# Prototype_0_2.net
KiCad netlist of a schematic drawn in EAGLE
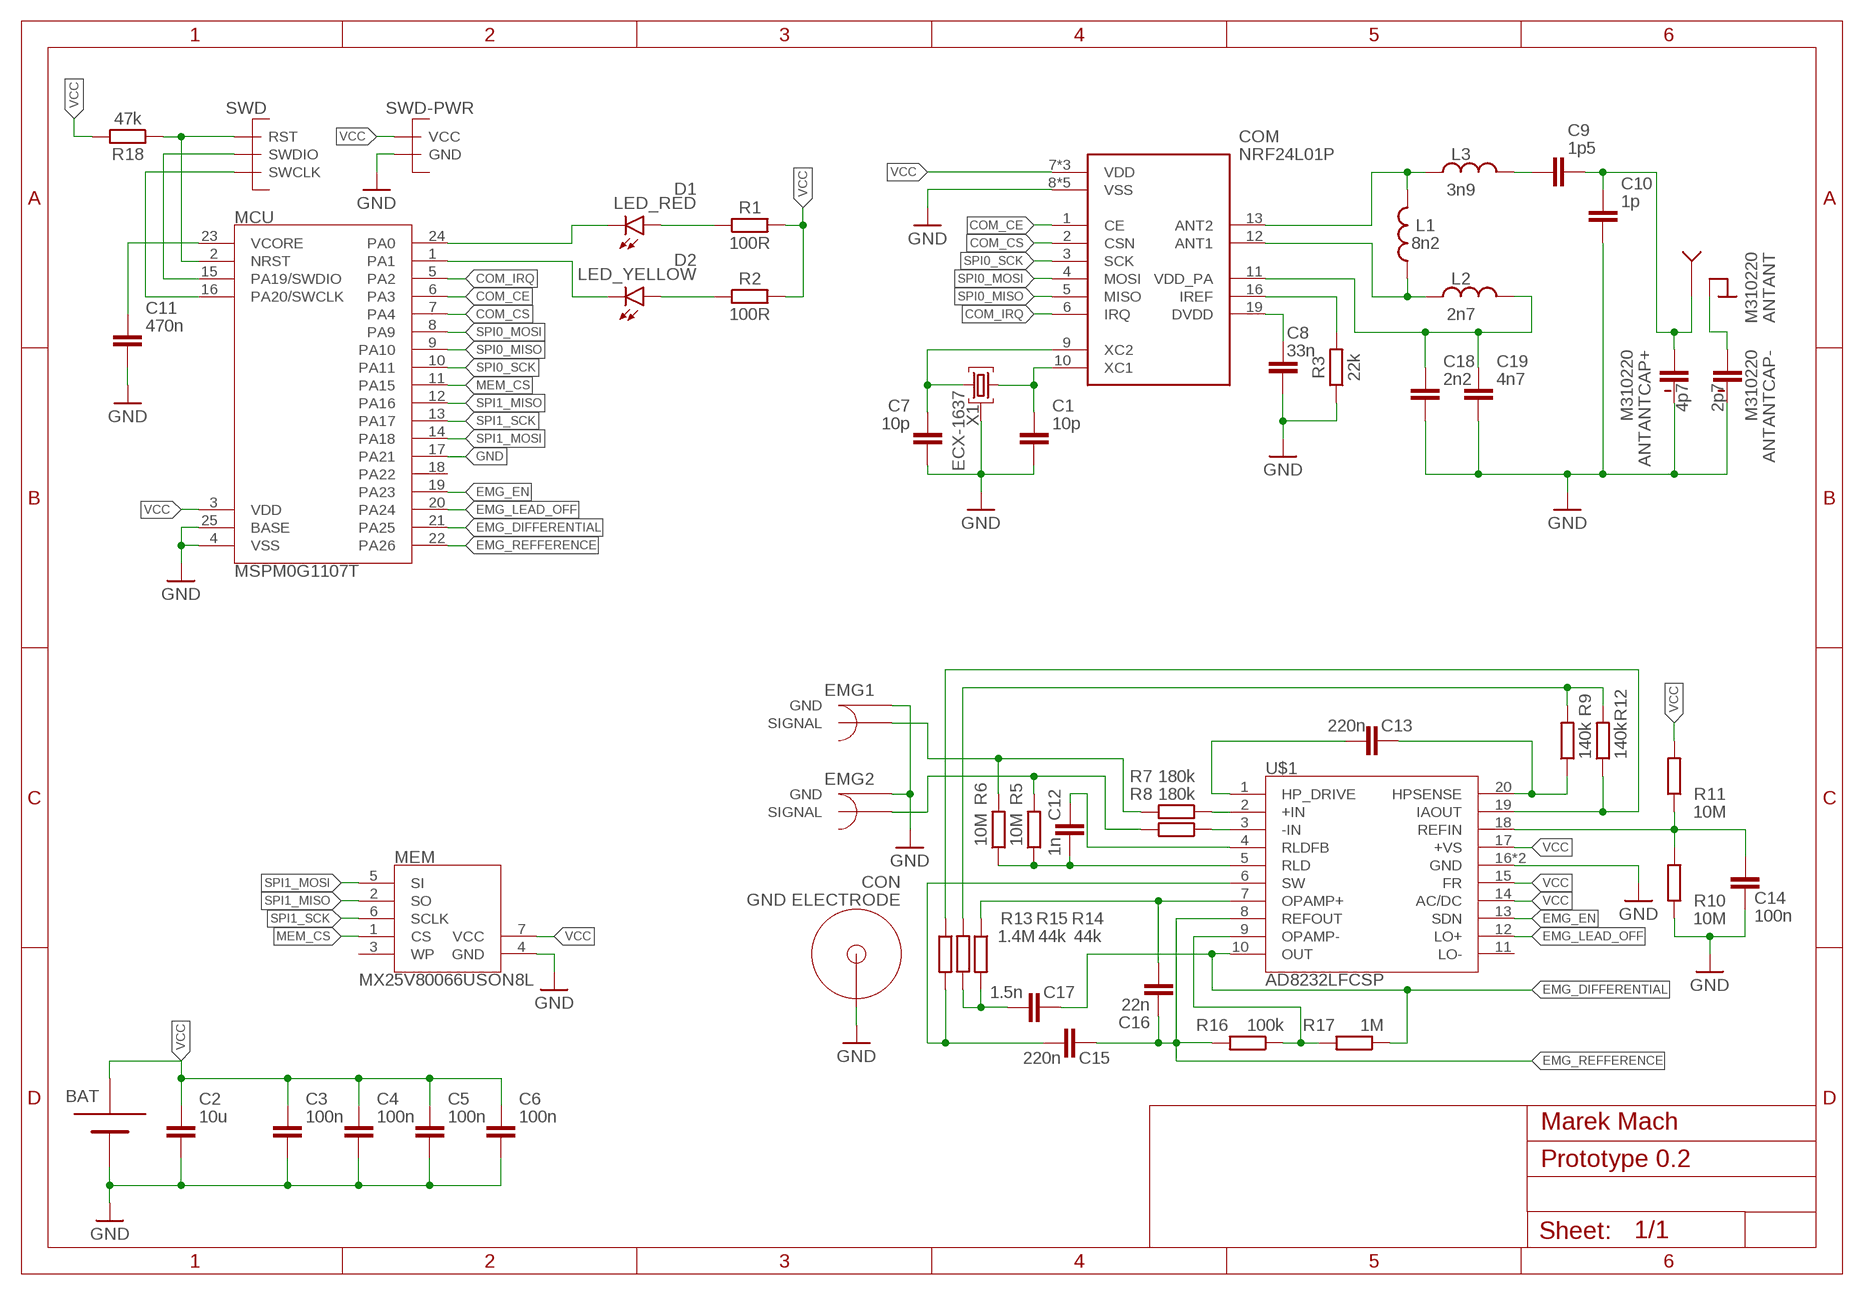
[diagram p0: schematic, sheet 1]

(export (version "E")
  (design (tool "Eeschema 10.0.6"))
  (components
    (comp (ref "ANT")
      (value "M310220")
      (footprint "eagle-import:M310220")
      (libsource (lib "eagle-import") (part "M310220"))
    )
    (comp (ref "BAT")
      (value "2025BAT-HLD-005-THM")
      (footprint "eagle-import:BAT-HLD-005-THM")
      (libsource (lib "eagle-import") (part "2025BAT-HLD-005-THM"))
    )
    (comp (ref "C1")
      (value "10p")
      (footprint "eagle-import:CAPC1005X60")
      (libsource (lib "eagle-import") (part "CCHIP-0402(1005-METRIC)_"))
    )
    (comp (ref "C2")
      (value "10u")
      (footprint "eagle-import:CAPC1608X85")
      (libsource (lib "eagle-import") (part "CCHIP-0603(1608-METRIC)_"))
    )
    (comp (ref "C3")
      (value "100n")
      (footprint "eagle-import:CAPC1608X85")
      (libsource (lib "eagle-import") (part "CCHIP-0603(1608-METRIC)_"))
    )
    (comp (ref "C4")
      (value "100n")
      (footprint "eagle-import:CAPC1608X85")
      (libsource (lib "eagle-import") (part "CCHIP-0603(1608-METRIC)_"))
    )
    (comp (ref "C5")
      (value "100n")
      (footprint "eagle-import:CAPC1608X85")
      (libsource (lib "eagle-import") (part "CCHIP-0603(1608-METRIC)_"))
    )
    (comp (ref "C6")
      (value "100n")
      (footprint "eagle-import:CAPC1608X85")
      (libsource (lib "eagle-import") (part "CCHIP-0603(1608-METRIC)_"))
    )
    (comp (ref "C7")
      (value "10p")
      (footprint "eagle-import:CAPC1005X60")
      (libsource (lib "eagle-import") (part "CCHIP-0402(1005-METRIC)_"))
    )
    (comp (ref "C8")
      (value "33n")
      (footprint "eagle-import:CAPC1005X60")
      (libsource (lib "eagle-import") (part "CCHIP-0402(1005-METRIC)_"))
    )
    (comp (ref "C9")
      (value "1p5")
      (footprint "eagle-import:CAPC1005X60")
      (libsource (lib "eagle-import") (part "CCHIP-0402(1005-METRIC)_"))
    )
    (comp (ref "C10")
      (value "1p")
      (footprint "eagle-import:CAPC1005X60")
      (libsource (lib "eagle-import") (part "CCHIP-0402(1005-METRIC)_"))
    )
    (comp (ref "C11")
      (value "470n")
      (footprint "eagle-import:CAPC1608X85")
      (libsource (lib "eagle-import") (part "CCHIP-0603(1608-METRIC)_"))
    )
    (comp (ref "C12")
      (value "1n")
      (footprint "eagle-import:CAPC1608X85")
      (libsource (lib "eagle-import") (part "CCHIP-0603(1608-METRIC)_"))
    )
    (comp (ref "C13")
      (value "220n")
      (footprint "eagle-import:CAPC1608X85")
      (libsource (lib "eagle-import") (part "CCHIP-0603(1608-METRIC)_"))
    )
    (comp (ref "C14")
      (value "100n")
      (footprint "eagle-import:CAPC1608X85")
      (libsource (lib "eagle-import") (part "CCHIP-0603(1608-METRIC)_"))
    )
    (comp (ref "C15")
      (value "220n")
      (footprint "eagle-import:CAPC1608X85")
      (libsource (lib "eagle-import") (part "CCHIP-0603(1608-METRIC)_"))
    )
    (comp (ref "C16")
      (value "22n")
      (footprint "eagle-import:CAPC1608X85")
      (libsource (lib "eagle-import") (part "CCHIP-0603(1608-METRIC)_"))
    )
    (comp (ref "C17")
      (value "1.5n")
      (footprint "eagle-import:CAPC1608X85")
      (libsource (lib "eagle-import") (part "CCHIP-0603(1608-METRIC)_"))
    )
    (comp (ref "C18")
      (value "2n2")
      (footprint "eagle-import:CAPC1005X60")
      (libsource (lib "eagle-import") (part "CCHIP-0402(1005-METRIC)_"))
    )
    (comp (ref "C19")
      (value "4n7")
      (footprint "eagle-import:CAPC1005X60")
      (libsource (lib "eagle-import") (part "CCHIP-0402(1005-METRIC)_"))
    )
    (comp (ref "COM")
      (value "NRF24L01P")
      (footprint "eagle-import:QFN50P400X400X100-21T265")
      (libsource (lib "eagle-import") (part "NRF24L01PQFN20"))
    )
    (comp (ref "CON")
      (value "GND ELECTRODE")
      (footprint "eagle-import:ELECTRODE_CONNECTOR")
      (libsource (lib "eagle-import") (part "ECG_ELECTRODE_CONNECTOR"))
    )
    (comp (ref "D1")
      (value "LED_RED")
      (footprint "eagle-import:LEDC1005X25N_FLAT-R")
      (libsource (lib "eagle-import") (part "CHIP-FLAT-R_0402"))
    )
    (comp (ref "D2")
      (value "LED_YELLOW")
      (footprint "eagle-import:LEDC1005X25N_FLAT-Y")
      (libsource (lib "eagle-import") (part "CHIP-FLAT-Y_0402"))
    )
    (comp (ref "EMG1")
      (value "SHIELDED-CONNECTOR")
      (footprint "eagle-import:SHIELDED-SMD")
      (libsource (lib "eagle-import") (part "SHIELDED-CONNECTOR"))
    )
    (comp (ref "EMG2")
      (value "SHIELDED-CONNECTOR")
      (footprint "eagle-import:SHIELDED-SMD")
      (libsource (lib "eagle-import") (part "SHIELDED-CONNECTOR"))
    )
    (comp (ref "L1")
      (value "8n2")
      (footprint "eagle-import:INDC1006X60N")
      (libsource (lib "eagle-import") (part "LCHIP-0402(1006-METRIC)_"))
    )
    (comp (ref "L2")
      (value "2n7")
      (footprint "eagle-import:INDC1006X60N")
      (libsource (lib "eagle-import") (part "LCHIP-0402(1006-METRIC)_"))
    )
    (comp (ref "L3")
      (value "3n9")
      (footprint "eagle-import:INDC1006X60N")
      (libsource (lib "eagle-import") (part "LCHIP-0402(1006-METRIC)_"))
    )
    (comp (ref "MCU")
      (value "MSPM0G1107T")
      (footprint "eagle-import:QFN50P400X400X100-25T240")
      (libsource (lib "eagle-import") (part "MSPM0G1107VQFN24-ROUNDPADS"))
    )
    (comp (ref "MEM")
      (value "MX25V80066USON8L")
      (footprint "eagle-import:SON50P300X200X50-8")
      (libsource (lib "eagle-import") (part "MX25V80066USON8L"))
    )
    (comp (ref "R1")
      (value "100R")
      (footprint "eagle-import:RESC1608X60")
      (libsource (lib "eagle-import") (part "RCHIP-0603(1608-METRIC)_"))
    )
    (comp (ref "R2")
      (value "100R")
      (footprint "eagle-import:RESC1608X60")
      (libsource (lib "eagle-import") (part "RCHIP-0603(1608-METRIC)_"))
    )
    (comp (ref "R3")
      (value "22k")
      (footprint "eagle-import:RESC1005X40")
      (libsource (lib "eagle-import") (part "RCHIP-0402(1005-METRIC)_"))
    )
    (comp (ref "R5")
      (value "10M")
      (footprint "eagle-import:RESC1608X60")
      (libsource (lib "eagle-import") (part "RCHIP-0603(1608-METRIC)_"))
    )
    (comp (ref "R6")
      (value "10M")
      (footprint "eagle-import:RESC1608X60")
      (libsource (lib "eagle-import") (part "RCHIP-0603(1608-METRIC)_"))
    )
    (comp (ref "R7")
      (value "180k")
      (footprint "eagle-import:RESC1608X60")
      (libsource (lib "eagle-import") (part "RCHIP-0603(1608-METRIC)_"))
    )
    (comp (ref "R8")
      (value "180k")
      (footprint "eagle-import:RESC1608X60")
      (libsource (lib "eagle-import") (part "RCHIP-0603(1608-METRIC)_"))
    )
    (comp (ref "R9")
      (value "140k")
      (footprint "eagle-import:RESC1608X60")
      (libsource (lib "eagle-import") (part "RCHIP-0603(1608-METRIC)_"))
    )
    (comp (ref "R10")
      (value "10M")
      (footprint "eagle-import:RESC1608X60")
      (libsource (lib "eagle-import") (part "RCHIP-0603(1608-METRIC)_"))
    )
    (comp (ref "R11")
      (value "10M")
      (footprint "eagle-import:RESC1608X60")
      (libsource (lib "eagle-import") (part "RCHIP-0603(1608-METRIC)_"))
    )
    (comp (ref "R12")
      (value "140k")
      (footprint "eagle-import:RESC1608X60")
      (libsource (lib "eagle-import") (part "RCHIP-0603(1608-METRIC)_"))
    )
    (comp (ref "R13")
      (value "1.4M")
      (footprint "eagle-import:RESC1608X60")
      (libsource (lib "eagle-import") (part "RCHIP-0603(1608-METRIC)_"))
    )
    (comp (ref "R14")
      (value "44k")
      (footprint "eagle-import:RESC1608X60")
      (libsource (lib "eagle-import") (part "RCHIP-0603(1608-METRIC)_"))
    )
    (comp (ref "R15")
      (value "44k")
      (footprint "eagle-import:RESC1608X60")
      (libsource (lib "eagle-import") (part "RCHIP-0603(1608-METRIC)_"))
    )
    (comp (ref "R16")
      (value "100k")
      (footprint "eagle-import:RESC1608X60")
      (libsource (lib "eagle-import") (part "RCHIP-0603(1608-METRIC)_"))
    )
    (comp (ref "R17")
      (value "1M")
      (footprint "eagle-import:RESC1608X60")
      (libsource (lib "eagle-import") (part "RCHIP-0603(1608-METRIC)_"))
    )
    (comp (ref "R18")
      (value "47k")
      (footprint "eagle-import:RESC1608X60")
      (libsource (lib "eagle-import") (part "RCHIP-0603(1608-METRIC)_"))
    )
    (comp (ref "SWD")
      (value "SWD")
      (footprint "eagle-import:3X")
      (libsource (lib "eagle-import") (part "SWD"))
    )
    (comp (ref "SWD-PWR")
      (value "PWR")
      (footprint "eagle-import:2X")
      (libsource (lib "eagle-import") (part "PWR"))
    )
    (comp (ref "U$1")
      (value "AD8232LFCSP")
      (footprint "eagle-import:QFN50P400X400X80-21T275")
      (libsource (lib "eagle-import") (part "AD8232LFCSP"))
    )
    (comp (ref "X1")
      (value "ECX-1637")
      (footprint "eagle-import:WE-XTAL_IQXC-42")
      (libsource (lib "eagle-import") (part "ECX-1637"))
    )
  )
  (nets
    (net (code "1") (name "COM_CE") (class "Default")
      (node (ref "COM") (pin "1") (pinfunction "CE_1") (pintype "bidirectional"))
      (node (ref "MCU") (pin "6") (pinfunction "PA3_6") (pintype "bidirectional"))
    )
    (net (code "2") (name "COM_CS") (class "Default")
      (node (ref "COM") (pin "2") (pinfunction "CSN_2") (pintype "input"))
      (node (ref "MCU") (pin "7") (pinfunction "PA4_7") (pintype "bidirectional"))
    )
    (net (code "3") (name "COM_IRQ") (class "Default")
      (node (ref "COM") (pin "6") (pinfunction "IRQ_6") (pintype "bidirectional"))
      (node (ref "MCU") (pin "5") (pinfunction "PA2_5") (pintype "bidirectional"))
    )
    (net (code "4") (name "EMG_DIFFERENTIAL") (class "Default")
      (node (ref "C17") (pin "2") (pinfunction "2_2") (pintype "passive"))
      (node (ref "MCU") (pin "21") (pinfunction "PA25_21") (pintype "bidirectional"))
      (node (ref "R17") (pin "1") (pinfunction "1_1") (pintype "passive"))
      (node (ref "U$1") (pin "10") (pinfunction "OUT_10") (pintype "bidirectional"))
    )
    (net (code "5") (name "EMG_EN") (class "Default")
      (node (ref "MCU") (pin "19") (pinfunction "PA23_19") (pintype "bidirectional"))
      (node (ref "U$1") (pin "13") (pinfunction "SDN_13") (pintype "bidirectional"))
    )
    (net (code "6") (name "EMG_LEAD_OFF") (class "Default")
      (node (ref "MCU") (pin "20") (pinfunction "PA24_20") (pintype "bidirectional"))
      (node (ref "U$1") (pin "12") (pinfunction "LO+_12") (pintype "bidirectional"))
    )
    (net (code "7") (name "EMG_REFFERENCE") (class "Default")
      (node (ref "C15") (pin "2") (pinfunction "2_2") (pintype "passive"))
      (node (ref "C16") (pin "1") (pinfunction "1_1") (pintype "passive"))
      (node (ref "MCU") (pin "22") (pinfunction "PA26_22") (pintype "bidirectional"))
      (node (ref "R16") (pin "2") (pinfunction "2_2") (pintype "passive"))
      (node (ref "U$1") (pin "8") (pinfunction "REFOUT_8") (pintype "bidirectional"))
    )
    (net (code "8") (name "GND") (class "Default")
      (node (ref "ANT") (pin "FEEDCAP-GND") (pinfunction "NEG_FEEDCAP-GND") (pintype "passive"))
      (node (ref "ANT") (pin "GNDCAP-GND") (pinfunction "NEG_GNDCAP-GND") (pintype "passive"))
      (node (ref "BAT") (pin "P$1") (pinfunction "-_P$1") (pintype "bidirectional"))
      (node (ref "C1") (pin "2") (pinfunction "2_2") (pintype "passive"))
      (node (ref "C10") (pin "2") (pinfunction "2_2") (pintype "passive"))
      (node (ref "C11") (pin "2") (pinfunction "2_2") (pintype "passive"))
      (node (ref "C14") (pin "1") (pinfunction "1_1") (pintype "passive"))
      (node (ref "C18") (pin "2") (pinfunction "2_2") (pintype "passive"))
      (node (ref "C19") (pin "2") (pinfunction "2_2") (pintype "passive"))
      (node (ref "C2") (pin "2") (pinfunction "2_2") (pintype "passive"))
      (node (ref "C3") (pin "2") (pinfunction "2_2") (pintype "passive"))
      (node (ref "C4") (pin "2") (pinfunction "2_2") (pintype "passive"))
      (node (ref "C5") (pin "2") (pinfunction "2_2") (pintype "passive"))
      (node (ref "C6") (pin "2") (pinfunction "2_2") (pintype "passive"))
      (node (ref "C7") (pin "2") (pinfunction "2_2") (pintype "passive"))
      (node (ref "C8") (pin "2") (pinfunction "2_2") (pintype "passive"))
      (node (ref "COM") (pin "14") (pinfunction "VSS_14") (pintype "power_in"))
      (node (ref "COM") (pin "17") (pinfunction "VSS_17") (pintype "power_in"))
      (node (ref "COM") (pin "20") (pinfunction "VSS_20") (pintype "power_in"))
      (node (ref "COM") (pin "21") (pinfunction "VSS_21") (pintype "power_in"))
      (node (ref "COM") (pin "8") (pinfunction "VSS_8") (pintype "power_in"))
      (node (ref "CON") (pin "P$1") (pinfunction "P$1_P$1") (pintype "bidirectional"))
      (node (ref "CON") (pin "P$2") (pinfunction "P$1_P$2") (pintype "bidirectional"))
      (node (ref "CON") (pin "P$3") (pinfunction "P$1_P$3") (pintype "bidirectional"))
      (node (ref "CON") (pin "P$4") (pinfunction "P$1_P$4") (pintype "bidirectional"))
      (node (ref "EMG1") (pin "GND1") (pinfunction "GND_GND1") (pintype "bidirectional"))
      (node (ref "EMG1") (pin "GND2") (pinfunction "GND_GND2") (pintype "bidirectional"))
      (node (ref "EMG2") (pin "GND1") (pinfunction "GND_GND1") (pintype "bidirectional"))
      (node (ref "EMG2") (pin "GND2") (pinfunction "GND_GND2") (pintype "bidirectional"))
      (node (ref "MCU") (pin "17") (pinfunction "PA21_17") (pintype "bidirectional"))
      (node (ref "MCU") (pin "25") (pinfunction "BASE_25") (pintype "bidirectional"))
      (node (ref "MCU") (pin "4") (pinfunction "VSS_4") (pintype "bidirectional"))
      (node (ref "MEM") (pin "4") (pinfunction "GND_4") (pintype "power_in"))
      (node (ref "R10") (pin "1") (pinfunction "1_1") (pintype "passive"))
      (node (ref "R3") (pin "1") (pinfunction "1_1") (pintype "passive"))
      (node (ref "SWD-PWR") (pin "1") (pinfunction "GND_1") (pintype "bidirectional"))
      (node (ref "U$1") (pin "16") (pinfunction "GND_16") (pintype "bidirectional"))
      (node (ref "U$1") (pin "21") (pinfunction "GND_21") (pintype "bidirectional"))
      (node (ref "X1") (pin "2") (pinfunction "GND_2") (pintype "passive"))
      (node (ref "X1") (pin "4") (pinfunction "GND_4") (pintype "passive"))
    )
    (net (code "9") (name "MEM_CS") (class "Default")
      (node (ref "MCU") (pin "11") (pinfunction "PA15_11") (pintype "bidirectional"))
      (node (ref "MEM") (pin "1") (pinfunction "CS_1") (pintype "bidirectional"))
    )
    (net (code "10") (name "Net-(ANTA-ANTENNA)") (class "Default")
      (node (ref "ANT") (pin "FEED") (pinfunction "ANTENNA_FEED") (pintype "input"))
      (node (ref "ANT") (pin "FEEDCAP-ANT") (pinfunction "POS_FEEDCAP-ANT") (pintype "passive"))
      (node (ref "C10") (pin "1") (pinfunction "1_1") (pintype "passive"))
      (node (ref "C9") (pin "2") (pinfunction "2_2") (pintype "passive"))
    )
    (net (code "11") (name "Net-(ANTA-P$1)") (class "Default")
      (node (ref "ANT") (pin "GNDCAP-GROUND") (pinfunction "POS_GNDCAP-GROUND") (pintype "passive"))
      (node (ref "ANT") (pin "GROUND") (pinfunction "P$1_GROUND") (pintype "bidirectional"))
    )
    (net (code "12") (name "Net-(C9-Pad1)") (class "Default")
      (node (ref "C9") (pin "1") (pinfunction "1_1") (pintype "passive"))
      (node (ref "L3") (pin "2") (pinfunction "2_2") (pintype "passive"))
    )
    (net (code "13") (name "Net-(C17-Pad1)") (class "Default")
      (node (ref "C17") (pin "1") (pinfunction "1_1") (pintype "passive"))
      (node (ref "R14") (pin "2") (pinfunction "2_2") (pintype "passive"))
      (node (ref "R15") (pin "1") (pinfunction "1_1") (pintype "passive"))
    )
    (net (code "14") (name "Net-(COM-ANT1)") (class "Default")
      (node (ref "COM") (pin "12") (pinfunction "ANT1_12") (pintype "bidirectional"))
      (node (ref "L1") (pin "1") (pinfunction "1_1") (pintype "passive"))
      (node (ref "L2") (pin "1") (pinfunction "1_1") (pintype "passive"))
    )
    (net (code "15") (name "Net-(COM-ANT2)") (class "Default")
      (node (ref "COM") (pin "13") (pinfunction "ANT2_13") (pintype "bidirectional"))
      (node (ref "L1") (pin "2") (pinfunction "2_2") (pintype "passive"))
      (node (ref "L3") (pin "1") (pinfunction "1_1") (pintype "passive"))
    )
    (net (code "16") (name "Net-(COM-DVDD)") (class "Default")
      (node (ref "C8") (pin "1") (pinfunction "1_1") (pintype "passive"))
      (node (ref "COM") (pin "19") (pinfunction "DVDD_19") (pintype "power_in"))
    )
    (net (code "17") (name "Net-(COM-IREF)") (class "Default")
      (node (ref "COM") (pin "16") (pinfunction "IREF_16") (pintype "input"))
      (node (ref "R3") (pin "2") (pinfunction "2_2") (pintype "passive"))
    )
    (net (code "18") (name "Net-(COM-VDD_PA)") (class "Default")
      (node (ref "C18") (pin "1") (pinfunction "1_1") (pintype "passive"))
      (node (ref "C19") (pin "1") (pinfunction "1_1") (pintype "passive"))
      (node (ref "COM") (pin "11") (pinfunction "VDD_PA_11") (pintype "power_in"))
      (node (ref "L2") (pin "2") (pinfunction "2_2") (pintype "passive"))
    )
    (net (code "19") (name "Net-(COM-XC1)") (class "Default")
      (node (ref "C1") (pin "1") (pinfunction "1_1") (pintype "passive"))
      (node (ref "COM") (pin "10") (pinfunction "XC1_10") (pintype "bidirectional"))
      (node (ref "X1") (pin "1") (pinfunction "1_1") (pintype "passive"))
    )
    (net (code "20") (name "Net-(COM-XC2)") (class "Default")
      (node (ref "C7") (pin "1") (pinfunction "1_1") (pintype "passive"))
      (node (ref "COM") (pin "9") (pinfunction "XC2_9") (pintype "bidirectional"))
      (node (ref "X1") (pin "3") (pinfunction "2_3") (pintype "passive"))
    )
    (net (code "21") (name "Net-(D1-PadA)") (class "Default")
      (node (ref "D1") (pin "A") (pinfunction "A_A") (pintype "passive"))
      (node (ref "R1") (pin "1") (pinfunction "1_1") (pintype "passive"))
    )
    (net (code "22") (name "Net-(D2-PadA)") (class "Default")
      (node (ref "D2") (pin "A") (pinfunction "A_A") (pintype "passive"))
      (node (ref "R2") (pin "1") (pinfunction "1_1") (pintype "passive"))
    )
    (net (code "23") (name "Net-(EMG1-SIGNAL)") (class "Default")
      (node (ref "EMG1") (pin "SIG") (pinfunction "SIGNAL_SIG") (pintype "bidirectional"))
      (node (ref "R6") (pin "2") (pinfunction "2_2") (pintype "passive"))
      (node (ref "R7") (pin "2") (pinfunction "2_2") (pintype "passive"))
    )
    (net (code "24") (name "Net-(EMG2-SIGNAL)") (class "Default")
      (node (ref "EMG2") (pin "SIG") (pinfunction "SIGNAL_SIG") (pintype "bidirectional"))
      (node (ref "R5") (pin "2") (pinfunction "2_2") (pintype "passive"))
      (node (ref "R8") (pin "2") (pinfunction "2_2") (pintype "passive"))
    )
    (net (code "25") (name "Net-(MCU-NRST)") (class "Default")
      (node (ref "MCU") (pin "2") (pinfunction "NRST_2") (pintype "bidirectional"))
      (node (ref "R18") (pin "1") (pinfunction "1_1") (pintype "passive"))
      (node (ref "SWD") (pin "1") (pinfunction "RST_1") (pintype "bidirectional"))
    )
    (net (code "26") (name "Net-(MCU-PA0)") (class "Default")
      (node (ref "D1") (pin "C") (pinfunction "C_C") (pintype "passive"))
      (node (ref "MCU") (pin "24") (pinfunction "PA0_24") (pintype "bidirectional"))
    )
    (net (code "27") (name "Net-(MCU-PA1)") (class "Default")
      (node (ref "D2") (pin "C") (pinfunction "C_C") (pintype "passive"))
      (node (ref "MCU") (pin "1") (pinfunction "PA1_1") (pintype "bidirectional"))
    )
    (net (code "28") (name "Net-(MCU-PA19{slash}SWDIO)") (class "Default")
      (node (ref "MCU") (pin "15") (pinfunction "PA19/SWDIO_15") (pintype "bidirectional"))
      (node (ref "SWD") (pin "2") (pinfunction "SWDIO_2") (pintype "bidirectional"))
    )
    (net (code "29") (name "Net-(MCU-PA20{slash}SWCLK)") (class "Default")
      (node (ref "MCU") (pin "16") (pinfunction "PA20/SWCLK_16") (pintype "bidirectional"))
      (node (ref "SWD") (pin "3") (pinfunction "SWCLK_3") (pintype "bidirectional"))
    )
    (net (code "30") (name "Net-(MCU-VCORE)") (class "Default")
      (node (ref "C11") (pin "1") (pinfunction "1_1") (pintype "passive"))
      (node (ref "MCU") (pin "23") (pinfunction "VCORE_23") (pintype "bidirectional"))
    )
    (net (code "31") (name "Net-(R12-Pad2)") (class "Default")
      (node (ref "R12") (pin "2") (pinfunction "2_2") (pintype "passive"))
      (node (ref "R15") (pin "2") (pinfunction "2_2") (pintype "passive"))
      (node (ref "R9") (pin "2") (pinfunction "2_2") (pintype "passive"))
    )
    (net (code "32") (name "Net-(U$1-+IN)") (class "Default")
      (node (ref "R7") (pin "1") (pinfunction "1_1") (pintype "passive"))
      (node (ref "U$1") (pin "2") (pinfunction "+IN_2") (pintype "bidirectional"))
    )
    (net (code "33") (name "Net-(U$1--IN)") (class "Default")
      (node (ref "R8") (pin "1") (pinfunction "1_1") (pintype "passive"))
      (node (ref "U$1") (pin "3") (pinfunction "-IN_3") (pintype "bidirectional"))
    )
    (net (code "34") (name "Net-(U$1-HPSENSE)") (class "Default")
      (node (ref "C13") (pin "2") (pinfunction "2_2") (pintype "passive"))
      (node (ref "R9") (pin "1") (pinfunction "1_1") (pintype "passive"))
      (node (ref "U$1") (pin "20") (pinfunction "HPSENSE_20") (pintype "bidirectional"))
    )
    (net (code "35") (name "Net-(U$1-HP_DRIVE)") (class "Default")
      (node (ref "C13") (pin "1") (pinfunction "1_1") (pintype "passive"))
      (node (ref "U$1") (pin "1") (pinfunction "HP_DRIVE_1") (pintype "bidirectional"))
    )
    (net (code "36") (name "Net-(U$1-IAOUT)") (class "Default")
      (node (ref "R12") (pin "1") (pinfunction "1_1") (pintype "passive"))
      (node (ref "R13") (pin "1") (pinfunction "1_1") (pintype "passive"))
      (node (ref "U$1") (pin "19") (pinfunction "IAOUT_19") (pintype "bidirectional"))
    )
    (net (code "37") (name "Net-(U$1-OPAMP+)") (class "Default")
      (node (ref "C16") (pin "2") (pinfunction "2_2") (pintype "passive"))
      (node (ref "R14") (pin "1") (pinfunction "1_1") (pintype "passive"))
      (node (ref "U$1") (pin "7") (pinfunction "OPAMP+_7") (pintype "bidirectional"))
    )
    (net (code "38") (name "Net-(U$1-OPAMP-)") (class "Default")
      (node (ref "R16") (pin "1") (pinfunction "1_1") (pintype "passive"))
      (node (ref "R17") (pin "2") (pinfunction "2_2") (pintype "passive"))
      (node (ref "U$1") (pin "9") (pinfunction "OPAMP-_9") (pintype "bidirectional"))
    )
    (net (code "39") (name "Net-(U$1-REFIN)") (class "Default")
      (node (ref "C14") (pin "2") (pinfunction "2_2") (pintype "passive"))
      (node (ref "R10") (pin "2") (pinfunction "2_2") (pintype "passive"))
      (node (ref "R11") (pin "1") (pinfunction "1_1") (pintype "passive"))
      (node (ref "U$1") (pin "18") (pinfunction "REFIN_18") (pintype "bidirectional"))
    )
    (net (code "40") (name "Net-(U$1-RLD)") (class "Default")
      (node (ref "C12") (pin "1") (pinfunction "1_1") (pintype "passive"))
      (node (ref "R5") (pin "1") (pinfunction "1_1") (pintype "passive"))
      (node (ref "R6") (pin "1") (pinfunction "1_1") (pintype "passive"))
      (node (ref "U$1") (pin "5") (pinfunction "RLD_5") (pintype "bidirectional"))
    )
    (net (code "41") (name "Net-(U$1-RLDFB)") (class "Default")
      (node (ref "C12") (pin "2") (pinfunction "2_2") (pintype "passive"))
      (node (ref "U$1") (pin "4") (pinfunction "RLDFB_4") (pintype "bidirectional"))
    )
    (net (code "42") (name "Net-(U$1-SW)") (class "Default")
      (node (ref "C15") (pin "1") (pinfunction "1_1") (pintype "passive"))
      (node (ref "R13") (pin "2") (pinfunction "2_2") (pintype "passive"))
      (node (ref "U$1") (pin "6") (pinfunction "SW_6") (pintype "bidirectional"))
    )
    (net (code "43") (name "SPI0_MISO") (class "Default")
      (node (ref "COM") (pin "5") (pinfunction "MISO_5") (pintype "bidirectional"))
      (node (ref "MCU") (pin "9") (pinfunction "PA10_9") (pintype "bidirectional"))
    )
    (net (code "44") (name "SPI0_MOSI") (class "Default")
      (node (ref "COM") (pin "4") (pinfunction "MOSI_4") (pintype "bidirectional"))
      (node (ref "MCU") (pin "8") (pinfunction "PA9_8") (pintype "bidirectional"))
    )
    (net (code "45") (name "SPI0_SCK") (class "Default")
      (node (ref "COM") (pin "3") (pinfunction "SCK_3") (pintype "bidirectional"))
      (node (ref "MCU") (pin "10") (pinfunction "PA11_10") (pintype "bidirectional"))
    )
    (net (code "46") (name "SPI1_MISO") (class "Default")
      (node (ref "MCU") (pin "12") (pinfunction "PA16_12") (pintype "bidirectional"))
      (node (ref "MEM") (pin "2") (pinfunction "SO_2") (pintype "bidirectional"))
    )
    (net (code "47") (name "SPI1_MOSI") (class "Default")
      (node (ref "MCU") (pin "14") (pinfunction "PA18_14") (pintype "bidirectional"))
      (node (ref "MEM") (pin "5") (pinfunction "SI_5") (pintype "bidirectional"))
    )
    (net (code "48") (name "SPI1_SCK") (class "Default")
      (node (ref "MCU") (pin "13") (pinfunction "PA17_13") (pintype "bidirectional"))
      (node (ref "MEM") (pin "6") (pinfunction "SCLK_6") (pintype "bidirectional"))
    )
    (net (code "49") (name "VCC") (class "Default")
      (node (ref "BAT") (pin "P$2") (pinfunction "+_P$2") (pintype "bidirectional"))
      (node (ref "BAT") (pin "P$3") (pinfunction "+_P$3") (pintype "bidirectional"))
      (node (ref "C2") (pin "1") (pinfunction "1_1") (pintype "passive"))
      (node (ref "C3") (pin "1") (pinfunction "1_1") (pintype "passive"))
      (node (ref "C4") (pin "1") (pinfunction "1_1") (pintype "passive"))
      (node (ref "C5") (pin "1") (pinfunction "1_1") (pintype "passive"))
      (node (ref "C6") (pin "1") (pinfunction "1_1") (pintype "passive"))
      (node (ref "COM") (pin "15") (pinfunction "VDD_15") (pintype "power_in"))
      (node (ref "COM") (pin "18") (pinfunction "VDD_18") (pintype "power_in"))
      (node (ref "COM") (pin "7") (pinfunction "VDD_7") (pintype "power_in"))
      (node (ref "MCU") (pin "3") (pinfunction "VDD_3") (pintype "bidirectional"))
      (node (ref "MEM") (pin "7") (pinfunction "VCC_7") (pintype "power_in"))
      (node (ref "R1") (pin "2") (pinfunction "2_2") (pintype "passive"))
      (node (ref "R11") (pin "2") (pinfunction "2_2") (pintype "passive"))
      (node (ref "R18") (pin "2") (pinfunction "2_2") (pintype "passive"))
      (node (ref "R2") (pin "2") (pinfunction "2_2") (pintype "passive"))
      (node (ref "SWD-PWR") (pin "2") (pinfunction "VCC_2") (pintype "bidirectional"))
      (node (ref "U$1") (pin "14") (pinfunction "AC/DC_14") (pintype "bidirectional"))
      (node (ref "U$1") (pin "15") (pinfunction "FR_15") (pintype "bidirectional"))
      (node (ref "U$1") (pin "17") (pinfunction "+VS_17") (pintype "bidirectional"))
    )
    (net (code "50") (name "unconnected-(MCU-PA22-Pad18)") (class "Default")
      (node (ref "MCU") (pin "18") (pinfunction "PA22_18") (pintype "bidirectional"))
    )
    (net (code "51") (name "unconnected-(MEM-WP-Pad3)") (class "Default")
      (node (ref "MEM") (pin "3") (pinfunction "WP_3") (pintype "bidirectional"))
    )
    (net (code "52") (name "unconnected-(U$1-LO--Pad11)") (class "Default")
      (node (ref "U$1") (pin "11") (pinfunction "LO-_11") (pintype "bidirectional"))
    )
  )
)
